# 13-Digital.net
KiCad netlist of a schematic drawn in Altium Designer
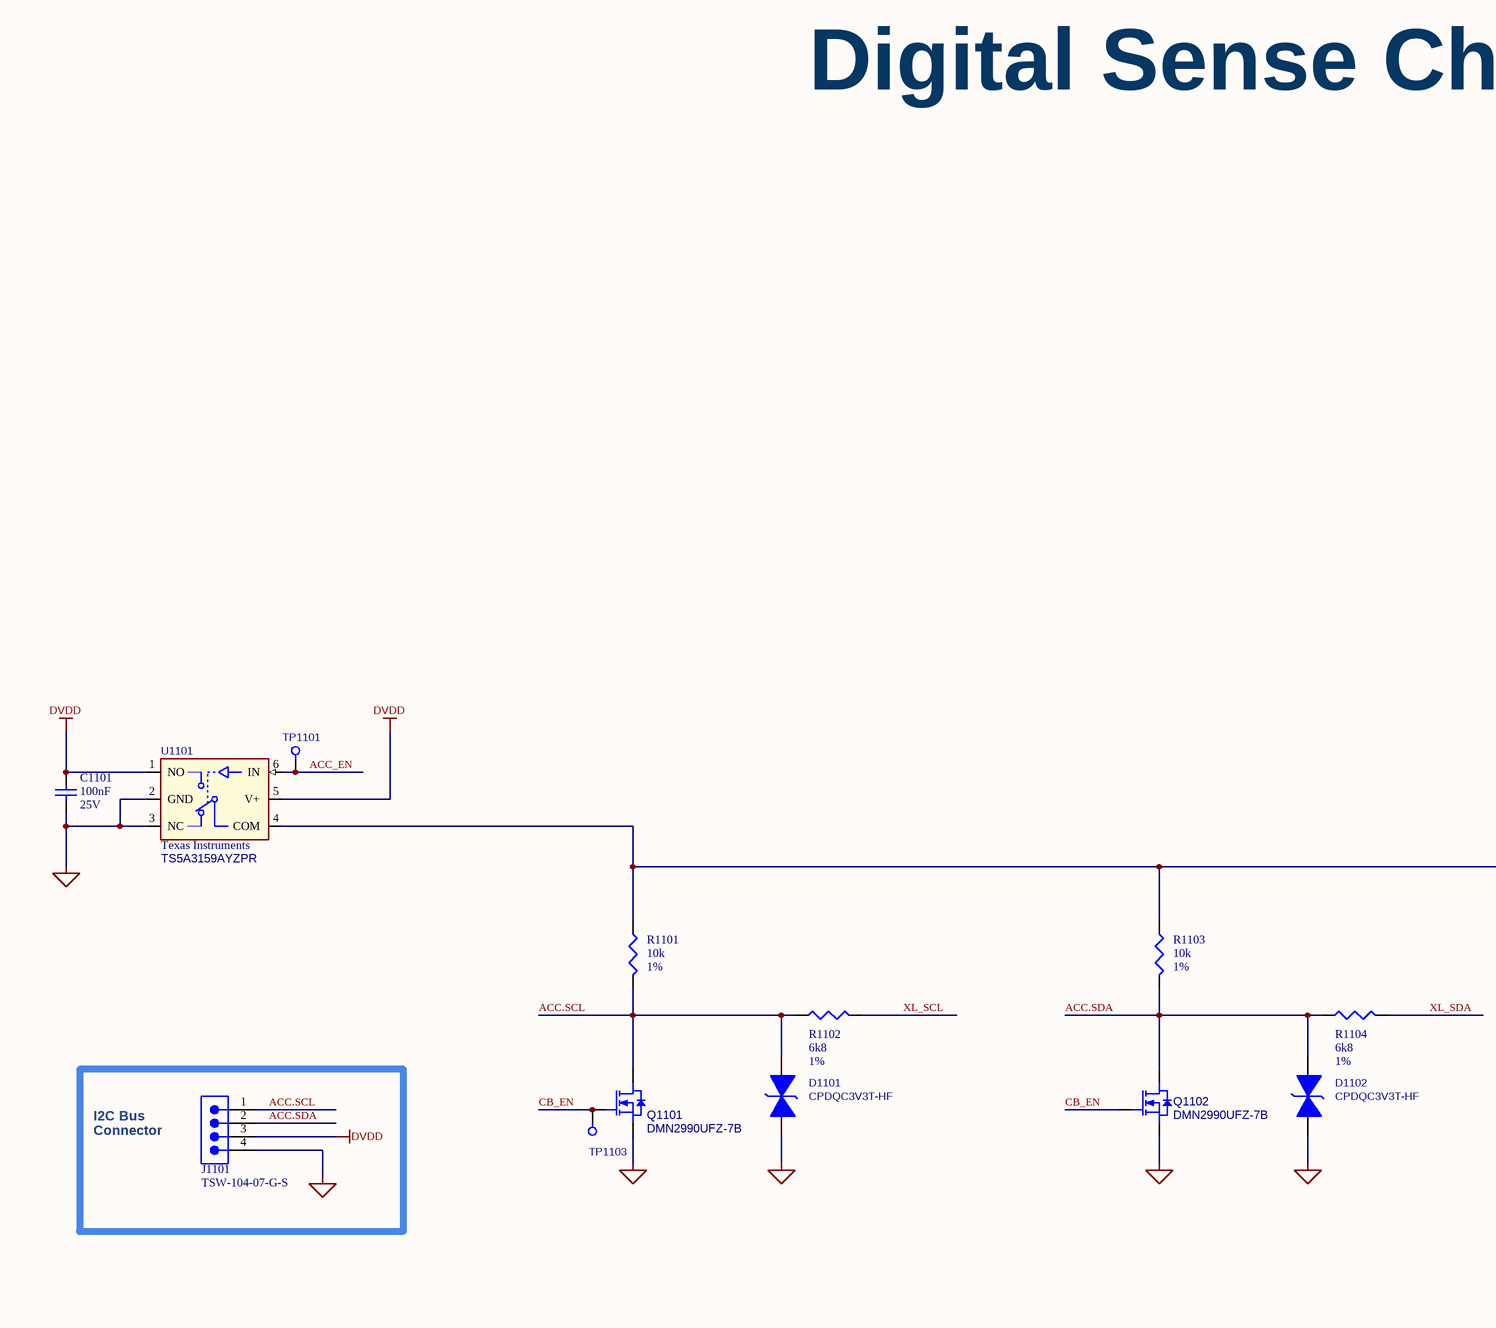
[diagram p0: 13-Digital.SchDoc, left]
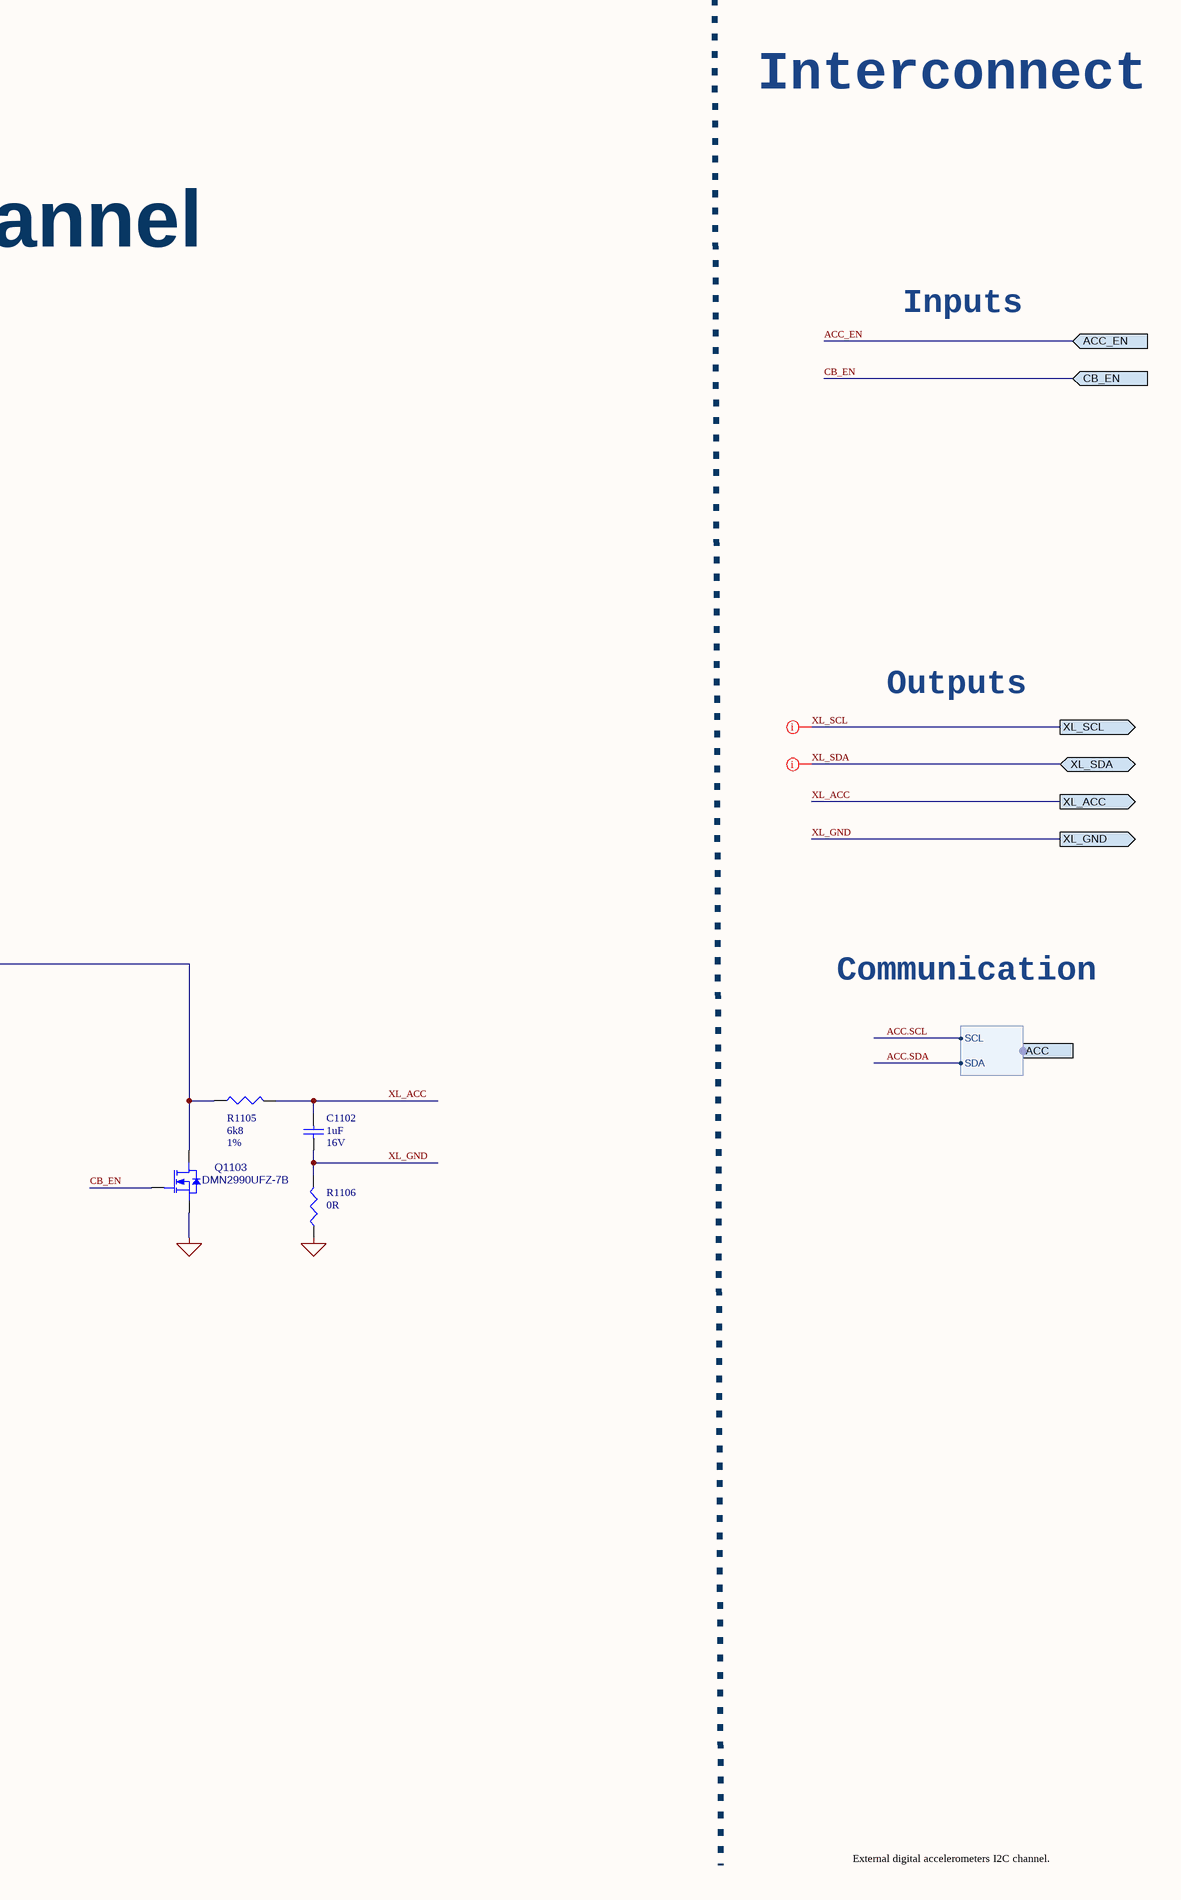
[diagram p1: 13-Digital.SchDoc, right]

(export (version "E")
  (design (tool "Eeschema 10.0.6"))
  (components
    (comp (ref "C1101")
      (value "100nF")
      (footprint "C0201_C")
      (fields
        (field (name "MANUFACTURER") "Murata")
        (field (name "MANUFACTURER PART NUMBER") "GRM033R61E104KE14J")
        (field (name "RATED DC VOLTAGE (URDC)") "25V")
      )
      (libsource (lib "MP-LIBRARY") (part "GRM033R61E104KE14J"))
    )
    (comp (ref "C1102")
      (value "1uF")
      (footprint "C0201_C")
      (fields
        (field (name "MANUFACTURER") "Murata")
        (field (name "MANUFACTURER PART NUMBER") "GRM033R61C105ME15D")
        (field (name "RATED DC VOLTAGE (URDC)") "16V")
      )
      (libsource (lib "MP-LIBRARY") (part "GRM033R61C105ME15D"))
    )
    (comp (ref "D1101")
      (value "CPDQC3V3T-HF")
      (footprint "0402C/SOD-923F")
      (description "ESD TVS DIODE 3.3VWM 6.2VC 0402C")
      (fields
        (field (name "MANUFACTURER") "Comchip Technology")
        (field (name "OCTOPART") "https://octopart.com/cpdqr5v0u-comchip-19043170")
      )
      (libsource (lib "MP-LIBRARY") (part "CPDQC3V3T-HF"))
    )
    (comp (ref "D1102")
      (value "CPDQC3V3T-HF")
      (footprint "0402C/SOD-923F")
      (description "ESD TVS DIODE 3.3VWM 6.2VC 0402C")
      (fields
        (field (name "MANUFACTURER") "Comchip Technology")
        (field (name "OCTOPART") "https://octopart.com/cpdqr5v0u-comchip-19043170")
      )
      (libsource (lib "MP-LIBRARY") (part "CPDQC3V3T-HF"))
    )
    (comp (ref "J1101")
      (value "TSW-104-07-G-S")
      (footprint "SMTC-TSW-104-07-X-S")
      (fields (field (name "MANUFACTURER") "Samtec") (field (name "PARTNUMBER") "TSW-106-07-G-S"))
      (libsource (lib "MP-LIBRARY") (part "TSW-104-07-G-S"))
    )
    (comp (ref "Q1101")
      (value "DMN2990UFZ-7B")
      (footprint "DIODESINC_X2-DFN0606-3")
      (description "MOSFET, N-Chan, 20V, 170mA, DFN0606")
      (fields (field (name "MANUFACTURER") "Diodes Inc"))
      (libsource (lib "MP-LIBRARY") (part "DMN2990UFZ-7B"))
    )
    (comp (ref "Q1102")
      (value "DMN2990UFZ-7B")
      (footprint "DIODESINC_X2-DFN0606-3")
      (description "MOSFET, N-Chan, 20V, 170mA, DFN0606")
      (fields (field (name "MANUFACTURER") "Diodes Inc"))
      (libsource (lib "MP-LIBRARY") (part "DMN2990UFZ-7B"))
    )
    (comp (ref "Q1103")
      (value "DMN2990UFZ-7B")
      (footprint "DIODESINC_X2-DFN0606-3")
      (description "MOSFET, N-Chan, 20V, 170mA, DFN0606")
      (fields (field (name "MANUFACTURER") "Diodes Inc"))
      (libsource (lib "MP-LIBRARY") (part "DMN2990UFZ-7B"))
    )
    (comp (ref "R1101")
      (value "10k")
      (footprint "R0201_C")
      (fields
        (field (name "TOLERANCE") "1%")
        (field (name "MANUFACTURER") "Vishay")
        (field (name "MANUFACTURER PART NUMBER") "CRCW020110K0FNED")
        (field (name "POWER") "50mW")
      )
      (libsource (lib "MP-LIBRARY") (part "CRCW020110K0FNED"))
    )
    (comp (ref "R1102")
      (value "6k8")
      (footprint "R0201_C")
      (fields
        (field (name "TOLERANCE") "1%")
        (field (name "MANUFACTURER") "Vishay")
        (field (name "MANUFACTURER PART NUMBER") "CRCW02016K80FNED")
        (field (name "POWER") "50mW")
      )
      (libsource (lib "MP-LIBRARY") (part "CRCW02016K80FNED"))
    )
    (comp (ref "R1103")
      (value "10k")
      (footprint "R0201_C")
      (fields
        (field (name "TOLERANCE") "1%")
        (field (name "MANUFACTURER") "Vishay")
        (field (name "MANUFACTURER PART NUMBER") "CRCW020110K0FNED")
        (field (name "POWER") "50mW")
      )
      (libsource (lib "MP-LIBRARY") (part "CRCW020110K0FNED"))
    )
    (comp (ref "R1104")
      (value "6k8")
      (footprint "R0201_C")
      (fields
        (field (name "TOLERANCE") "1%")
        (field (name "MANUFACTURER") "Vishay")
        (field (name "MANUFACTURER PART NUMBER") "CRCW02016K80FNED")
        (field (name "POWER") "50mW")
      )
      (libsource (lib "MP-LIBRARY") (part "CRCW02016K80FNED"))
    )
    (comp (ref "R1105")
      (value "6k8")
      (footprint "R0201_C")
      (fields
        (field (name "TOLERANCE") "1%")
        (field (name "MANUFACTURER") "Vishay")
        (field (name "MANUFACTURER PART NUMBER") "CRCW02016K80FNED")
        (field (name "POWER") "50mW")
      )
      (libsource (lib "MP-LIBRARY") (part "CRCW02016K80FNED"))
    )
    (comp (ref "R1106")
      (value "0R")
      (footprint "R0201_C")
      (description "Fixed Resistor, Metal Glaze/thick Film, 0.05W, 0ohm, Surface Mount, 0201")
      (fields
        (field (name "MANUFACTURER") "Vishay")
        (field (name "MANUFACTURER PART NUMBER") "CRCW02010000Z0ED")
      )
      (libsource (lib "MP-LIBRARY") (part "CRCW02010000Z0ED"))
    )
    (comp (ref "TP1101")
      (value "Test Point")
      (footprint "testpad_0.9mm")
      (description "Test pad, 0.90mm circular pad")
      (libsource (lib "MP-LIBRARY") (part "Test Point"))
    )
    (comp (ref "TP1103")
      (value "Test Point")
      (footprint "testpad_0.9mm")
      (description "Test pad, 0.90mm circular pad")
      (libsource (lib "MP-LIBRARY") (part "Test Point"))
    )
    (comp (ref "U1101")
      (value "TS5A3159AYZPR")
      (footprint "TI_YZP6")
      (description "Analog Switch, SPDT, 2:1, DSBGA6")
      (fields (field (name "MANUFACTURER") "Texas Instruments"))
      (libsource (lib "MP-LIBRARY") (part "TS5A3159AYZPR"))
    )
  )
  (nets
    (net (code "2") (name "/ACC.SCL") (class "Default")
      (node (ref "D1101") (pin "2") (pinfunction "A_2") (pintype "passive"))
      (node (ref "J1101") (pin "1") (pinfunction "1_1") (pintype "passive"))
      (node (ref "Q1101") (pin "3") (pinfunction "D_3") (pintype "passive"))
      (node (ref "R1101") (pin "2") (pinfunction "2_2") (pintype "passive"))
      (node (ref "R1102") (pin "1") (pinfunction "1_1") (pintype "passive"))
    )
    (net (code "3") (name "/ACC.SDA") (class "Default")
      (node (ref "D1102") (pin "2") (pinfunction "A_2") (pintype "passive"))
      (node (ref "J1101") (pin "2") (pinfunction "2_2") (pintype "passive"))
      (node (ref "Q1102") (pin "3") (pinfunction "D_3") (pintype "passive"))
      (node (ref "R1103") (pin "2") (pinfunction "2_2") (pintype "passive"))
      (node (ref "R1104") (pin "1") (pinfunction "1_1") (pintype "passive"))
    )
    (net (code "4") (name "/ACC_EN") (class "Default")
      (node (ref "TP1101") (pin "1") (pinfunction "1_1") (pintype "passive"))
      (node (ref "U1101") (pin "6") (pinfunction "IN_6") (pintype "input"))
    )
    (net (code "5") (name "/CB_EN") (class "Default")
      (node (ref "Q1101") (pin "1") (pinfunction "G_1") (pintype "passive"))
      (node (ref "Q1102") (pin "1") (pinfunction "G_1") (pintype "passive"))
      (node (ref "Q1103") (pin "1") (pinfunction "G_1") (pintype "passive"))
      (node (ref "TP1103") (pin "1") (pinfunction "1_1") (pintype "passive"))
    )
    (net (code "6") (name "/XL_ACC") (class "Default")
      (node (ref "C1102") (pin "2") (pinfunction "2_2") (pintype "passive"))
      (node (ref "R1105") (pin "2") (pinfunction "2_2") (pintype "passive"))
    )
    (net (code "7") (name "/XL_GND") (class "Default")
      (node (ref "C1102") (pin "1") (pinfunction "1_1") (pintype "passive"))
      (node (ref "R1106") (pin "2") (pinfunction "2_2") (pintype "passive"))
    )
    (net (code "8") (name "/XL_SCL") (class "Default")
      (node (ref "R1102") (pin "2") (pinfunction "2_2") (pintype "passive"))
    )
    (net (code "9") (name "/XL_SDA") (class "Default")
      (node (ref "R1104") (pin "2") (pinfunction "2_2") (pintype "passive"))
    )
    (net (code "11") (name "DVDD") (class "Default")
      (node (ref "C1101") (pin "2") (pinfunction "2_2") (pintype "passive"))
      (node (ref "J1101") (pin "3") (pinfunction "3_3") (pintype "passive"))
      (node (ref "U1101") (pin "1") (pinfunction "NO_1") (pintype "passive"))
      (node (ref "U1101") (pin "5") (pinfunction "V+_5") (pintype "power_in"))
    )
    (net (code "12") (name "GND") (class "Default")
      (node (ref "C1101") (pin "1") (pinfunction "1_1") (pintype "passive"))
      (node (ref "D1101") (pin "1") (pinfunction "C_1") (pintype "passive"))
      (node (ref "D1102") (pin "1") (pinfunction "C_1") (pintype "passive"))
      (node (ref "J1101") (pin "4") (pinfunction "4_4") (pintype "passive"))
      (node (ref "Q1101") (pin "2") (pinfunction "S_2") (pintype "passive"))
      (node (ref "Q1102") (pin "2") (pinfunction "S_2") (pintype "passive"))
      (node (ref "Q1103") (pin "2") (pinfunction "S_2") (pintype "passive"))
      (node (ref "R1106") (pin "1") (pinfunction "1_1") (pintype "passive"))
      (node (ref "U1101") (pin "2") (pinfunction "GND_2") (pintype "power_in"))
      (node (ref "U1101") (pin "3") (pinfunction "NC_3") (pintype "passive"))
    )
    (net (code "13") (name "Net-(Q1103-D)") (class "Default")
      (node (ref "Q1103") (pin "3") (pinfunction "D_3") (pintype "passive"))
      (node (ref "R1101") (pin "1") (pinfunction "1_1") (pintype "passive"))
      (node (ref "R1103") (pin "1") (pinfunction "1_1") (pintype "passive"))
      (node (ref "R1105") (pin "1") (pinfunction "1_1") (pintype "passive"))
      (node (ref "U1101") (pin "4") (pinfunction "COM_4") (pintype "passive"))
    )
  )
)
